# True_Variant.net
KiCad netlist of a schematic drawn in Altium Designer
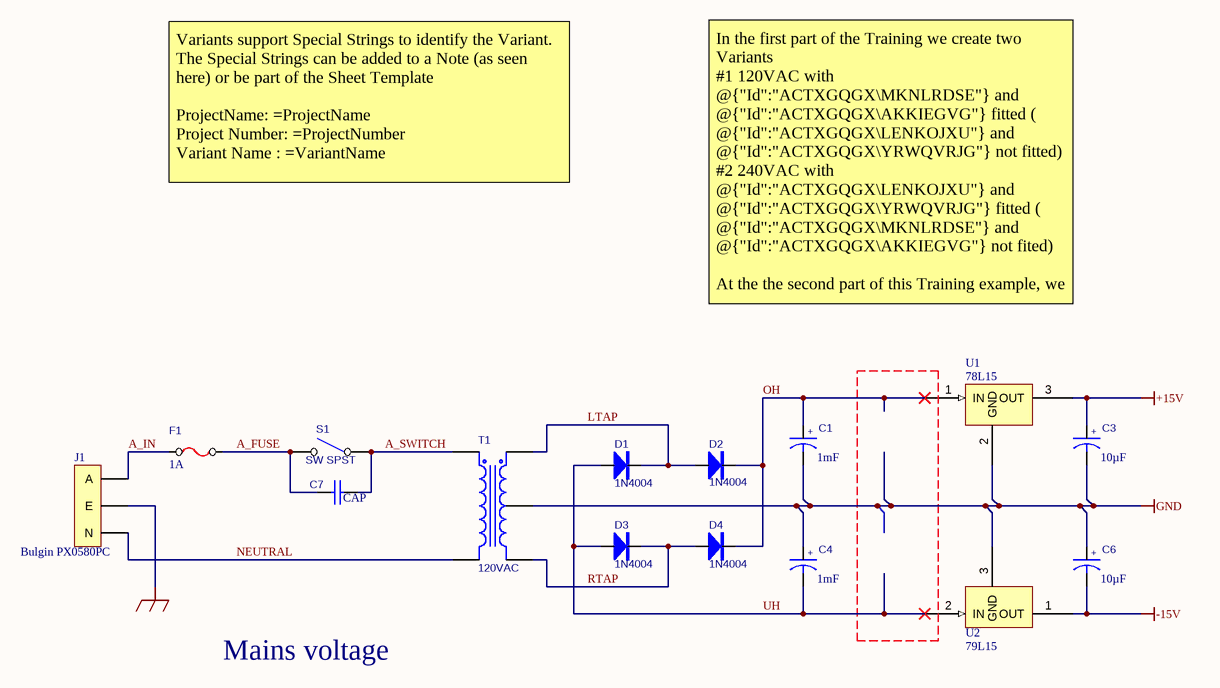
[diagram p0: True Variant.SchDoc]

(export (version "E")
  (design (tool "Eeschema 10.0.6"))
  (components
    (comp (ref "C1")
      (value "1mF")
      (footprint "RB.4_.8")
      (description "Bi-Polar Capacitor")
      (fields (field (name "Comment") "CAP1000uF"))
      (libsource (lib "MHH -  Altium Advanced Course A365 01") (part "CAP Polar Training"))
    )
    (comp (ref "C3")
      (value "10µF")
      (footprint "RB.2_.4")
      (description "CAP-Polar 10uF")
      (fields (field (name "Comment") "CAP Polar 10uF"))
      (libsource (lib "MHH -  Altium Advanced Course A365 01") (part "CAP Polar Training"))
    )
    (comp (ref "C4")
      (value "1mF")
      (footprint "RB.4_.8")
      (description "Bi-Polar Capacitor")
      (fields (field (name "Comment") "CAP1000uF"))
      (libsource (lib "MHH -  Altium Advanced Course A365 01") (part "CAP Polar Training"))
    )
    (comp (ref "C6")
      (value "10µF")
      (footprint "RB.2_.4")
      (description "CAP-Polar 10uF")
      (fields (field (name "Comment") "CAP Polar 10uF"))
      (libsource (lib "MHH -  Altium Advanced Course A365 01") (part "CAP Polar Training"))
    )
    (comp (ref "C7")
      (value "CAP")
      (footprint "RAD0.8")
      (description "1nF / 2kV")
      (libsource (lib "MHH -  Altium Advanced Course A365 01") (part "CAP"))
    )
    (comp (ref "D1")
      (value "1N4004")
      (footprint "DIODE0.5")
      (libsource (lib "MHH -  Altium Advanced Course A365 01") (part "1N4004"))
    )
    (comp (ref "D2")
      (value "1N4004")
      (footprint "DIODE0.5")
      (libsource (lib "MHH -  Altium Advanced Course A365 01") (part "1N4004"))
    )
    (comp (ref "D3")
      (value "1N4004")
      (footprint "DIODE0.5")
      (libsource (lib "MHH -  Altium Advanced Course A365 01") (part "1N4004"))
    )
    (comp (ref "D4")
      (value "1N4004")
      (footprint "DIODE0.5")
      (libsource (lib "MHH -  Altium Advanced Course A365 01") (part "1N4004"))
    )
    (comp (ref "F1")
      (value "FUSE")
      (footprint "FUSE")
      (description "Fuse")
      (fields (field (name "CURRENT RATING") "1A"))
      (libsource (lib "MHH -  Altium Advanced Course A365 01") (part "FUSE"))
    )
    (comp (ref "J1")
      (value "Bulgin PX0580PC")
      (footprint "Bulgin PX0580PC")
      (libsource (lib "MHH -  Altium Advanced Course A365 01") (part "General  Power Connector"))
    )
    (comp (ref "S1")
      (value "SW SPST")
      (footprint "SW-MAINS")
      (description "Main Switch")
      (libsource (lib "MHH -  Altium Advanced Course A365 01") (part "SW SPST"))
    )
    (comp (ref "T1")
      (value "120VAC")
      (footprint "TRANSFORMER")
      (description "Center-Tapped Transformer")
      (libsource (lib "MHH -  Altium Advanced Course A365 01") (part "Center-Tapped Transformer"))
    )
    (comp (ref "U1")
      (value "78L15")
      (footprint "TO-92A")
      (description "Very Low Drop Voltage Regulators With Inhibit")
      (libsource (lib "MHH -  Altium Advanced Course A365 01") (part "78L15"))
    )
    (comp (ref "U2")
      (value "79L15")
      (footprint "TO-92A")
      (description "Very Low Drop Voltage Regulators With Inhibit")
      (libsource (lib "MHH -  Altium Advanced Course A365 01") (part "79L15"))
    )
  )
  (nets
    (net (code "1") (name "+15V") (class "Default")
      (node (ref "C3") (pin "1") (pinfunction "1_1") (pintype "passive"))
      (node (ref "U1") (pin "3") (pinfunction "OUT_3") (pintype "power_in"))
    )
    (net (code "2") (name "-15V") (class "Default")
      (node (ref "C6") (pin "2") (pinfunction "2_2") (pintype "passive"))
      (node (ref "U2") (pin "1") (pinfunction "OUT_1") (pintype "power_in"))
    )
    (net (code "3") (name "/A_FUSE") (class "Default")
      (node (ref "C7") (pin "2") (pinfunction "2_2") (pintype "passive"))
      (node (ref "F1") (pin "2") (pinfunction "2_2") (pintype "passive"))
      (node (ref "S1") (pin "2") (pinfunction "NO_2") (pintype "passive"))
    )
    (net (code "4") (name "/A_IN") (class "Default")
      (node (ref "F1") (pin "1") (pinfunction "1_1") (pintype "passive"))
      (node (ref "J1") (pin "1") (pinfunction "A_1") (pintype "passive"))
    )
    (net (code "5") (name "/A_SWITCH") (class "Default")
      (node (ref "C7") (pin "1") (pinfunction "1_1") (pintype "passive"))
      (node (ref "S1") (pin "1") (pinfunction "COMMON_1") (pintype "passive"))
      (node (ref "T1") (pin "1") (pinfunction "Pri+_1") (pintype "passive"))
    )
    (net (code "6") (name "/LTAP") (class "Default")
      (node (ref "D1") (pin "2") (pinfunction "K_2") (pintype "passive"))
      (node (ref "D2") (pin "1") (pinfunction "A_1") (pintype "passive"))
      (node (ref "T1") (pin "3") (pinfunction "Sec+_3") (pintype "passive"))
    )
    (net (code "7") (name "/NEUTRAL") (class "Default")
      (node (ref "J1") (pin "3") (pinfunction "N_3") (pintype "passive"))
      (node (ref "T1") (pin "2") (pinfunction "Pri-_2") (pintype "passive"))
    )
    (net (code "8") (name "/OH") (class "Default")
      (node (ref "C1") (pin "1") (pinfunction "1_1") (pintype "passive"))
      (node (ref "D2") (pin "2") (pinfunction "K_2") (pintype "passive"))
      (node (ref "D4") (pin "2") (pinfunction "K_2") (pintype "passive"))
      (node (ref "U1") (pin "1") (pinfunction "IN_1") (pintype "input"))
    )
    (net (code "9") (name "/RTAP") (class "Default")
      (node (ref "D3") (pin "2") (pinfunction "K_2") (pintype "passive"))
      (node (ref "D4") (pin "1") (pinfunction "A_1") (pintype "passive"))
      (node (ref "T1") (pin "5") (pinfunction "Sec-_5") (pintype "passive"))
    )
    (net (code "10") (name "/UH") (class "Default")
      (node (ref "C4") (pin "2") (pinfunction "2_2") (pintype "passive"))
      (node (ref "D1") (pin "1") (pinfunction "A_1") (pintype "passive"))
      (node (ref "D3") (pin "1") (pinfunction "A_1") (pintype "passive"))
      (node (ref "U2") (pin "2") (pinfunction "IN_2") (pintype "input"))
    )
    (net (code "11") (name "CHASSIS") (class "Default")
      (node (ref "J1") (pin "2") (pinfunction "E_2") (pintype "passive"))
    )
    (net (code "12") (name "GND") (class "Default")
      (node (ref "C1") (pin "2") (pinfunction "2_2") (pintype "passive"))
      (node (ref "C3") (pin "2") (pinfunction "2_2") (pintype "passive"))
      (node (ref "C4") (pin "1") (pinfunction "1_1") (pintype "passive"))
      (node (ref "C6") (pin "1") (pinfunction "1_1") (pintype "passive"))
      (node (ref "T1") (pin "4") (pinfunction "SecCT_4") (pintype "passive"))
      (node (ref "U1") (pin "2") (pinfunction "GND_2") (pintype "power_in"))
      (node (ref "U2") (pin "3") (pinfunction "GND_3") (pintype "power_in"))
    )
  )
)
